# LP3985-3_3-150mA.net
KiCad netlist of a schematic drawn in Altium Designer
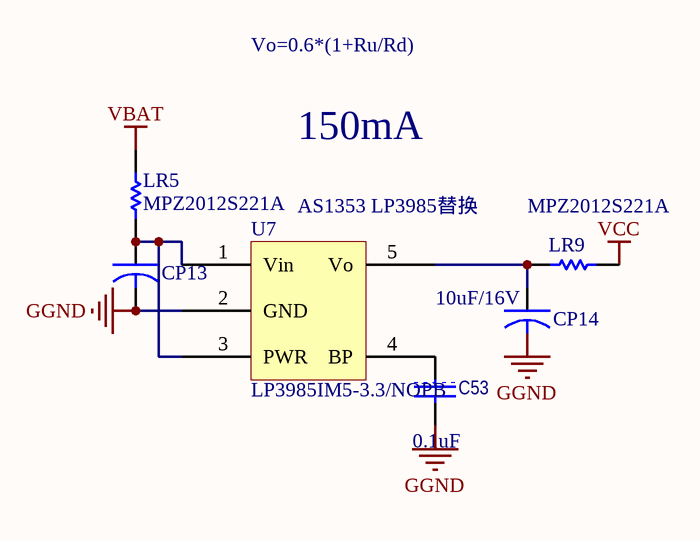
[diagram p0: LP3985-3.3-150mA_电源.SchDoc]

(export (version "E")
  (design (tool "Eeschema 10.0.6"))
  (components
    (comp (ref "C53")
      (value "0.1uF")
      (footprint "1608[0603]C")
      (description "多层陶瓷电容器MLCC - SMD/SMT 0603 0.1uF 50volts X7R 10%")
      (fields (field (name "MANUFACTURER") "TDK") (field (name "MANUFACTURER PART NUMBER") "C1608X7R1H104K"))
      (libsource (lib "*") (part "CAP"))
    )
    (comp (ref "CP13")
      (value "TAJA106K016RNJ")
      (footprint "3216[1206]CB")
      (description "钽质电容器-固体SMD 16volts 10uF 10%")
      (fields (field (name "MANUFACTURER") "AVX"))
      (libsource (lib "*") (part "CAPACITOR"))
    )
    (comp (ref "CP14")
      (value "10uF/16V")
      (footprint "3216[1206]CB")
      (description "钽质电容器-固体SMD 16volts 10uF 10%")
      (fields (field (name "MANUFACTURER") "AVX") (field (name "MANUFACTURER PART NUMBER") "TAJA106K016RNJ"))
      (libsource (lib "*") (part "CAPACITOR"))
    )
    (comp (ref "LR5")
      (value "MPZ2012S221A")
      (footprint "2012[0805]")
      (description "电磁干扰滤波珠子、扼流圈和阵列 Ferrite Chip Beads")
      (fields (field (name "MANUFACTURER") "TDK"))
      (libsource (lib "Miscellaneous Devices") (part "Res Semi"))
    )
    (comp (ref "LR9")
      (value "MPZ2012S221A")
      (footprint "2012[0805]")
      (description "电磁干扰滤波珠子、扼流圈和阵列 Ferrite Chip Beads")
      (fields (field (name "MANUFACTURER") "TDK"))
      (libsource (lib "Miscellaneous Devices") (part "Res Semi"))
    )
    (comp (ref "U7")
      (value "LP3985IM5-3.3/NOPB")
      (footprint "SOT23-5BN")
      (description "低压差稳压器 - LDO 150Ma Low Noise CMOS LDO")
      (fields (field (name "MANUFACTURER") "Texas Instruments"))
      (libsource (lib "S3C2440V9") (part "LT1761"))
    )
  )
  (nets
    (net (code "1") (name "GGND") (class "Default")
      (node (ref "C53") (pin "2") (pinfunction "2_2") (pintype "passive"))
      (node (ref "CP13") (pin "2") (pinfunction "2_2") (pintype "passive"))
      (node (ref "U7") (pin "2") (pinfunction "GND_2") (pintype "passive"))
    )
    (net (code "2") (name "Net-(U7-BP)") (class "Default")
      (node (ref "C53") (pin "1") (pinfunction "1_1") (pintype "passive"))
      (node (ref "U7") (pin "4") (pinfunction "BP_4") (pintype "passive"))
    )
    (net (code "3") (name "Net-(U7-PWR)") (class "Default")
      (node (ref "CP13") (pin "1") (pinfunction "1_1") (pintype "passive"))
      (node (ref "LR5") (pin "1") (pinfunction "1_1") (pintype "passive"))
      (node (ref "U7") (pin "1") (pinfunction "Vin_1") (pintype "passive"))
      (node (ref "U7") (pin "3") (pinfunction "PWR_3") (pintype "passive"))
    )
    (net (code "4") (name "Net-(U7-Vo)") (class "Default")
      (node (ref "CP14") (pin "1") (pinfunction "1_1") (pintype "passive"))
      (node (ref "LR9") (pin "2") (pinfunction "2_2") (pintype "passive"))
      (node (ref "U7") (pin "5") (pinfunction "Vo_5") (pintype "passive"))
    )
    (net (code "5") (name "VBAT") (class "Default")
      (node (ref "LR5") (pin "2") (pinfunction "2_2") (pintype "passive"))
    )
    (net (code "6") (name "VCC") (class "Default")
      (node (ref "LR9") (pin "1") (pinfunction "1_1") (pintype "passive"))
    )
    (net (code "7") (name "unconnected-(CP14-Pad2)") (class "Default")
      (node (ref "CP14") (pin "2") (pinfunction "2_2") (pintype "passive"))
    )
  )
)
